# child.net
KiCad netlist of a schematic drawn in EAGLE
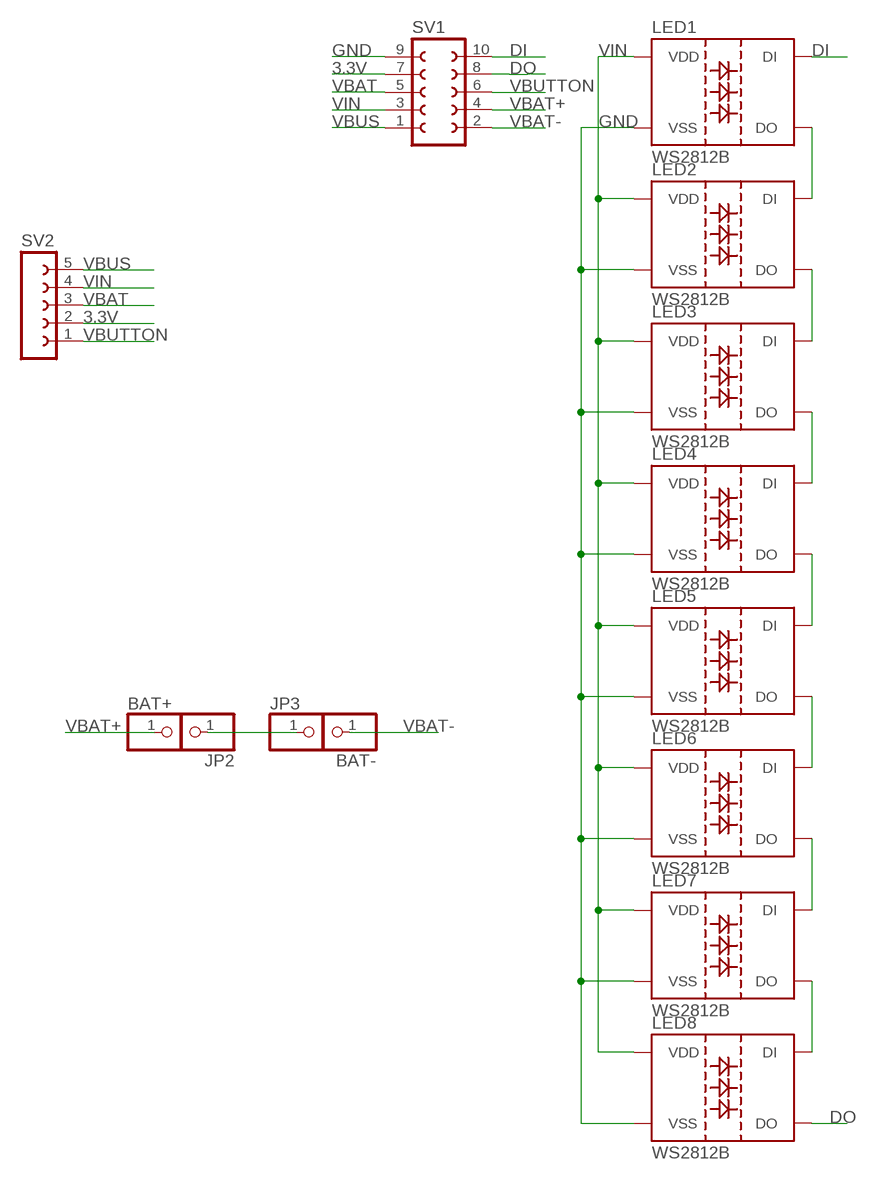
[diagram p0: schematic, sheet 1]

(export (version "E")
  (design (tool "Eeschema 10.0.6"))
  (components
    (comp (ref "BAT+")
      (value "PINHD-1X1")
      (footprint "eagle-import:1X01")
      (libsource (lib "eagle-import") (part "PINHD-1X1"))
    )
    (comp (ref "BAT-")
      (value "PINHD-1X1")
      (footprint "eagle-import:1X01")
      (libsource (lib "eagle-import") (part "PINHD-1X1"))
    )
    (comp (ref "JP2")
      (value "PINHD-1X1")
      (footprint "eagle-import:1X01")
      (libsource (lib "eagle-import") (part "PINHD-1X1"))
    )
    (comp (ref "JP3")
      (value "PINHD-1X1")
      (footprint "eagle-import:1X01")
      (libsource (lib "eagle-import") (part "PINHD-1X1"))
    )
    (comp (ref "LED1")
      (value "WS2812B")
      (footprint "eagle-import:WS2812B")
      (libsource (lib "eagle-import") (part "WS2812B"))
    )
    (comp (ref "LED2")
      (value "WS2812B")
      (footprint "eagle-import:WS2812B")
      (libsource (lib "eagle-import") (part "WS2812B"))
    )
    (comp (ref "LED3")
      (value "WS2812B")
      (footprint "eagle-import:WS2812B")
      (libsource (lib "eagle-import") (part "WS2812B"))
    )
    (comp (ref "LED4")
      (value "WS2812B")
      (footprint "eagle-import:WS2812B")
      (libsource (lib "eagle-import") (part "WS2812B"))
    )
    (comp (ref "LED5")
      (value "WS2812B")
      (footprint "eagle-import:WS2812B")
      (libsource (lib "eagle-import") (part "WS2812B"))
    )
    (comp (ref "LED6")
      (value "WS2812B")
      (footprint "eagle-import:WS2812B")
      (libsource (lib "eagle-import") (part "WS2812B"))
    )
    (comp (ref "LED7")
      (value "WS2812B")
      (footprint "eagle-import:WS2812B")
      (libsource (lib "eagle-import") (part "WS2812B"))
    )
    (comp (ref "LED8")
      (value "WS2812B")
      (footprint "eagle-import:WS2812B")
      (libsource (lib "eagle-import") (part "WS2812B"))
    )
    (comp (ref "SV1")
      (value "FE05-2W")
      (footprint "eagle-import:FE05-2W")
      (libsource (lib "eagle-import") (part "FE05-2W"))
    )
    (comp (ref "SV2")
      (value "FE05-1")
      (footprint "eagle-import:FE05-1")
      (libsource (lib "eagle-import") (part "FE05-1"))
    )
  )
  (nets
    (net (code "1") (name "/3.3V") (class "Default")
      (node (ref "SV1") (pin "7") (pinfunction "7_7") (pintype "passive"))
      (node (ref "SV2") (pin "2") (pinfunction "2_2") (pintype "passive"))
    )
    (net (code "2") (name "/DI") (class "Default")
      (node (ref "LED1") (pin "4") (pinfunction "DI_4") (pintype "bidirectional"))
      (node (ref "SV1") (pin "10") (pinfunction "10_10") (pintype "passive"))
    )
    (net (code "3") (name "/DO") (class "Default")
      (node (ref "LED8") (pin "2") (pinfunction "DO_2") (pintype "bidirectional"))
      (node (ref "SV1") (pin "8") (pinfunction "8_8") (pintype "passive"))
    )
    (net (code "4") (name "/GND") (class "Default")
      (node (ref "LED1") (pin "3") (pinfunction "VSS_3") (pintype "bidirectional"))
      (node (ref "LED2") (pin "3") (pinfunction "VSS_3") (pintype "bidirectional"))
      (node (ref "LED3") (pin "3") (pinfunction "VSS_3") (pintype "bidirectional"))
      (node (ref "LED4") (pin "3") (pinfunction "VSS_3") (pintype "bidirectional"))
      (node (ref "LED5") (pin "3") (pinfunction "VSS_3") (pintype "bidirectional"))
      (node (ref "LED6") (pin "3") (pinfunction "VSS_3") (pintype "bidirectional"))
      (node (ref "LED7") (pin "3") (pinfunction "VSS_3") (pintype "bidirectional"))
      (node (ref "LED8") (pin "3") (pinfunction "VSS_3") (pintype "bidirectional"))
      (node (ref "SV1") (pin "9") (pinfunction "9_9") (pintype "passive"))
    )
    (net (code "5") (name "/VBAT") (class "Default")
      (node (ref "SV1") (pin "5") (pinfunction "5_5") (pintype "passive"))
      (node (ref "SV2") (pin "3") (pinfunction "3_3") (pintype "passive"))
    )
    (net (code "6") (name "/VBAT+") (class "Default")
      (node (ref "BAT+") (pin "1") (pinfunction "1_1") (pintype "passive"))
      (node (ref "SV1") (pin "4") (pinfunction "4_4") (pintype "passive"))
    )
    (net (code "7") (name "/VBAT-") (class "Default")
      (node (ref "BAT-") (pin "1") (pinfunction "1_1") (pintype "passive"))
      (node (ref "SV1") (pin "2") (pinfunction "2_2") (pintype "passive"))
    )
    (net (code "8") (name "/VBUS") (class "Default")
      (node (ref "SV1") (pin "1") (pinfunction "1_1") (pintype "passive"))
      (node (ref "SV2") (pin "5") (pinfunction "5_5") (pintype "passive"))
    )
    (net (code "9") (name "/VBUTTON") (class "Default")
      (node (ref "SV1") (pin "6") (pinfunction "6_6") (pintype "passive"))
      (node (ref "SV2") (pin "1") (pinfunction "1_1") (pintype "passive"))
    )
    (net (code "10") (name "/VIN") (class "Default")
      (node (ref "LED1") (pin "1") (pinfunction "VDD_1") (pintype "bidirectional"))
      (node (ref "LED2") (pin "1") (pinfunction "VDD_1") (pintype "bidirectional"))
      (node (ref "LED3") (pin "1") (pinfunction "VDD_1") (pintype "bidirectional"))
      (node (ref "LED4") (pin "1") (pinfunction "VDD_1") (pintype "bidirectional"))
      (node (ref "LED5") (pin "1") (pinfunction "VDD_1") (pintype "bidirectional"))
      (node (ref "LED6") (pin "1") (pinfunction "VDD_1") (pintype "bidirectional"))
      (node (ref "LED7") (pin "1") (pinfunction "VDD_1") (pintype "bidirectional"))
      (node (ref "LED8") (pin "1") (pinfunction "VDD_1") (pintype "bidirectional"))
      (node (ref "SV1") (pin "3") (pinfunction "3_3") (pintype "passive"))
      (node (ref "SV2") (pin "4") (pinfunction "4_4") (pintype "passive"))
    )
    (net (code "11") (name "Net-(JP2-Pad1)") (class "Default")
      (node (ref "JP2") (pin "1") (pinfunction "1_1") (pintype "passive"))
      (node (ref "JP3") (pin "1") (pinfunction "1_1") (pintype "passive"))
    )
    (net (code "12") (name "Net-(LED1-DO)") (class "Default")
      (node (ref "LED1") (pin "2") (pinfunction "DO_2") (pintype "bidirectional"))
      (node (ref "LED2") (pin "4") (pinfunction "DI_4") (pintype "bidirectional"))
    )
    (net (code "13") (name "Net-(LED2-DO)") (class "Default")
      (node (ref "LED2") (pin "2") (pinfunction "DO_2") (pintype "bidirectional"))
      (node (ref "LED3") (pin "4") (pinfunction "DI_4") (pintype "bidirectional"))
    )
    (net (code "14") (name "Net-(LED3-DO)") (class "Default")
      (node (ref "LED3") (pin "2") (pinfunction "DO_2") (pintype "bidirectional"))
      (node (ref "LED4") (pin "4") (pinfunction "DI_4") (pintype "bidirectional"))
    )
    (net (code "15") (name "Net-(LED4-DO)") (class "Default")
      (node (ref "LED4") (pin "2") (pinfunction "DO_2") (pintype "bidirectional"))
      (node (ref "LED5") (pin "4") (pinfunction "DI_4") (pintype "bidirectional"))
    )
    (net (code "16") (name "Net-(LED5-DO)") (class "Default")
      (node (ref "LED5") (pin "2") (pinfunction "DO_2") (pintype "bidirectional"))
      (node (ref "LED6") (pin "4") (pinfunction "DI_4") (pintype "bidirectional"))
    )
    (net (code "17") (name "Net-(LED6-DO)") (class "Default")
      (node (ref "LED6") (pin "2") (pinfunction "DO_2") (pintype "bidirectional"))
      (node (ref "LED7") (pin "4") (pinfunction "DI_4") (pintype "bidirectional"))
    )
    (net (code "18") (name "Net-(LED7-DO)") (class "Default")
      (node (ref "LED7") (pin "2") (pinfunction "DO_2") (pintype "bidirectional"))
      (node (ref "LED8") (pin "4") (pinfunction "DI_4") (pintype "bidirectional"))
    )
  )
)
